# cc_gen_and_heat_pwr.net
KiCad netlist of a schematic drawn in Altium Designer
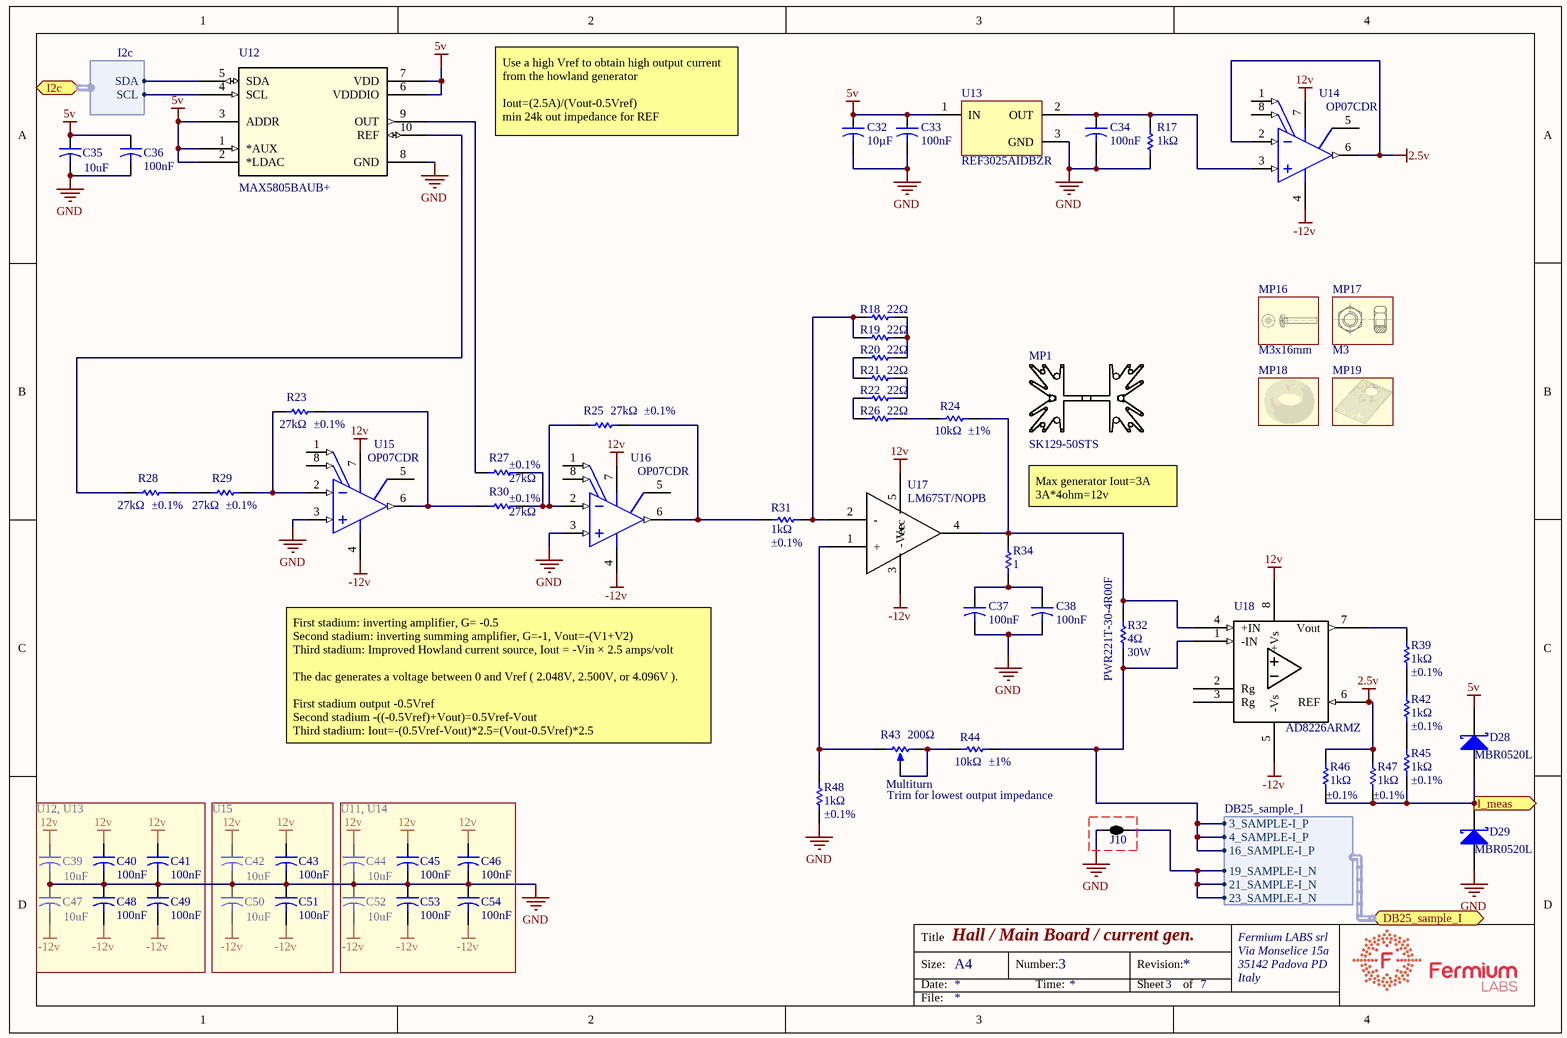
[diagram p0: cc_gen_and_heat_pwr.SchDoc]

(export (version "E")
  (design (tool "Eeschema 10.0.6"))
  (components
    (comp (ref "C32")
      (value "~")
      (footprint "Passives:CAP 1206/3216")
      (description "Capacitor")
      (fields
        (field (name "MANUFACTURER") "SAMSUNG")
        (field (name "MANUFACTURER PART NUMBER") "CL31A106KAHNNNE")
        (field (name "CAPACITANCE") "10µF")
        (field (name "PUBLISHER") "Altium Limited")
      )
      (libsource (lib "Miscellaneous Devices") (part "Cap2"))
    )
    (comp (ref "C33")
      (value "~")
      (footprint "Passives:CAP 0805/2012")
      (description "Capacitor")
      (fields
        (field (name "CAPACITANCE") "100nF")
        (field (name "MANUFACTURER") "YAGEO")
        (field (name "MANUFACTURER PART NUMBER") "CC0805JRX7R9BB104")
      )
      (libsource (lib "Miscellaneous Devices") (part "Cap2"))
    )
    (comp (ref "C34")
      (value "~")
      (footprint "Passives:CAP 0805/2012")
      (description "Capacitor")
      (fields
        (field (name "CAPACITANCE") "100nF")
        (field (name "MANUFACTURER") "YAGEO")
        (field (name "MANUFACTURER PART NUMBER") "CC0805JRX7R9BB104")
      )
      (libsource (lib "Miscellaneous Devices") (part "Cap2"))
    )
    (comp (ref "C35")
      (value "10uF")
      (footprint "Passives:CAP 1206/3216")
      (description "Capacitor")
      (fields
        (field (name "MANUFACTURER") "SAMSUNG")
        (field (name "MANUFACTURER PART NUMBER") "CL31A106KAHNNNE")
        (field (name "PUBLISHER") "Altium Limited")
      )
      (libsource (lib "Miscellaneous Devices") (part "Cap2"))
    )
    (comp (ref "C36")
      (value "~")
      (footprint "Passives:CAP 0805/2012")
      (description "Capacitor")
      (fields
        (field (name "CAPACITANCE") "100nF")
        (field (name "MANUFACTURER") "YAGEO")
        (field (name "MANUFACTURER PART NUMBER") "CC0805JRX7R9BB104")
      )
      (libsource (lib "") (part "Cap2_1"))
    )
    (comp (ref "C37")
      (value "~")
      (footprint "Passives:CAP 0805/2012")
      (description "Capacitor")
      (fields
        (field (name "CAPACITANCE") "100nF")
        (field (name "MANUFACTURER") "YAGEO")
        (field (name "MANUFACTURER PART NUMBER") "CC0805JRX7R9BB104")
      )
      (libsource (lib "Miscellaneous Devices") (part "Cap2"))
    )
    (comp (ref "C38")
      (value "~")
      (footprint "Passives:CAP 0805/2012")
      (description "Capacitor")
      (fields
        (field (name "CAPACITANCE") "100nF")
        (field (name "MANUFACTURER") "YAGEO")
        (field (name "MANUFACTURER PART NUMBER") "CC0805JRX7R9BB104")
      )
      (libsource (lib "Miscellaneous Devices") (part "Cap2"))
    )
    (comp (ref "C39")
      (value "10uF")
      (footprint "Passives:CAP 1206/3216")
      (description "Capacitor")
      (fields
        (field (name "MANUFACTURER") "SAMSUNG")
        (field (name "MANUFACTURER PART NUMBER") "CL31A106KAHNNNE")
        (field (name "PUBLISHER") "Altium Limited")
      )
      (libsource (lib "Miscellaneous Devices") (part "Cap2"))
    )
    (comp (ref "C40")
      (value "~")
      (footprint "Passives:CAP 0805/2012")
      (description "Capacitor")
      (fields
        (field (name "CAPACITANCE") "100nF")
        (field (name "MANUFACTURER") "YAGEO")
        (field (name "MANUFACTURER PART NUMBER") "CC0805JRX7R9BB104")
      )
      (libsource (lib "") (part "Cap2_1"))
    )
    (comp (ref "C41")
      (value "~")
      (footprint "Passives:CAP 0805/2012")
      (description "Capacitor")
      (fields
        (field (name "CAPACITANCE") "100nF")
        (field (name "MANUFACTURER") "YAGEO")
        (field (name "MANUFACTURER PART NUMBER") "CC0805JRX7R9BB104")
      )
      (libsource (lib "") (part "Cap2_1"))
    )
    (comp (ref "C42")
      (value "10uF")
      (footprint "Passives:CAP 1206/3216")
      (description "Capacitor")
      (fields
        (field (name "MANUFACTURER") "SAMSUNG")
        (field (name "MANUFACTURER PART NUMBER") "CL31A106KAHNNNE")
        (field (name "PUBLISHER") "Altium Limited")
      )
      (libsource (lib "Miscellaneous Devices") (part "Cap2"))
    )
    (comp (ref "C43")
      (value "~")
      (footprint "Passives:CAP 0805/2012")
      (description "Capacitor")
      (fields
        (field (name "CAPACITANCE") "100nF")
        (field (name "MANUFACTURER") "YAGEO")
        (field (name "MANUFACTURER PART NUMBER") "CC0805JRX7R9BB104")
      )
      (libsource (lib "") (part "Cap2_1"))
    )
    (comp (ref "C44")
      (value "10uF")
      (footprint "Passives:CAP 1206/3216")
      (description "Capacitor")
      (fields
        (field (name "MANUFACTURER") "SAMSUNG")
        (field (name "MANUFACTURER PART NUMBER") "CL31A106KAHNNNE")
        (field (name "PUBLISHER") "Altium Limited")
      )
      (libsource (lib "Miscellaneous Devices") (part "Cap2"))
    )
    (comp (ref "C45")
      (value "~")
      (footprint "Passives:CAP 0805/2012")
      (description "Capacitor")
      (fields
        (field (name "CAPACITANCE") "100nF")
        (field (name "MANUFACTURER") "YAGEO")
        (field (name "MANUFACTURER PART NUMBER") "CC0805JRX7R9BB104")
      )
      (libsource (lib "") (part "Cap2_1"))
    )
    (comp (ref "C46")
      (value "~")
      (footprint "Passives:CAP 0805/2012")
      (description "Capacitor")
      (fields
        (field (name "CAPACITANCE") "100nF")
        (field (name "MANUFACTURER") "YAGEO")
        (field (name "MANUFACTURER PART NUMBER") "CC0805JRX7R9BB104")
      )
      (libsource (lib "") (part "Cap2_1"))
    )
    (comp (ref "C47")
      (value "10uF")
      (footprint "Passives:CAP 1206/3216")
      (description "Capacitor")
      (fields
        (field (name "MANUFACTURER") "SAMSUNG")
        (field (name "MANUFACTURER PART NUMBER") "CL31A106KAHNNNE")
        (field (name "PUBLISHER") "Altium Limited")
      )
      (libsource (lib "Miscellaneous Devices") (part "Cap2"))
    )
    (comp (ref "C48")
      (value "~")
      (footprint "Passives:CAP 0805/2012")
      (description "Capacitor")
      (fields
        (field (name "CAPACITANCE") "100nF")
        (field (name "MANUFACTURER") "YAGEO")
        (field (name "MANUFACTURER PART NUMBER") "CC0805JRX7R9BB104")
      )
      (libsource (lib "") (part "Cap2_1"))
    )
    (comp (ref "C49")
      (value "~")
      (footprint "Passives:CAP 0805/2012")
      (description "Capacitor")
      (fields
        (field (name "CAPACITANCE") "100nF")
        (field (name "MANUFACTURER") "YAGEO")
        (field (name "MANUFACTURER PART NUMBER") "CC0805JRX7R9BB104")
      )
      (libsource (lib "") (part "Cap2_1"))
    )
    (comp (ref "C50")
      (value "10uF")
      (footprint "Passives:CAP 1206/3216")
      (description "Capacitor")
      (fields
        (field (name "MANUFACTURER") "SAMSUNG")
        (field (name "MANUFACTURER PART NUMBER") "CL31A106KAHNNNE")
        (field (name "PUBLISHER") "Altium Limited")
      )
      (libsource (lib "Miscellaneous Devices") (part "Cap2"))
    )
    (comp (ref "C51")
      (value "~")
      (footprint "Passives:CAP 0805/2012")
      (description "Capacitor")
      (fields
        (field (name "CAPACITANCE") "100nF")
        (field (name "MANUFACTURER") "YAGEO")
        (field (name "MANUFACTURER PART NUMBER") "CC0805JRX7R9BB104")
      )
      (libsource (lib "") (part "Cap2_1"))
    )
    (comp (ref "C52")
      (value "10uF")
      (footprint "Passives:CAP 1206/3216")
      (description "Capacitor")
      (fields
        (field (name "MANUFACTURER") "SAMSUNG")
        (field (name "MANUFACTURER PART NUMBER") "CL31A106KAHNNNE")
        (field (name "PUBLISHER") "Altium Limited")
      )
      (libsource (lib "Miscellaneous Devices") (part "Cap2"))
    )
    (comp (ref "C53")
      (value "~")
      (footprint "Passives:CAP 0805/2012")
      (description "Capacitor")
      (fields
        (field (name "CAPACITANCE") "100nF")
        (field (name "MANUFACTURER") "YAGEO")
        (field (name "MANUFACTURER PART NUMBER") "CC0805JRX7R9BB104")
      )
      (libsource (lib "") (part "Cap2_1"))
    )
    (comp (ref "C54")
      (value "~")
      (footprint "Passives:CAP 0805/2012")
      (description "Capacitor")
      (fields
        (field (name "CAPACITANCE") "100nF")
        (field (name "MANUFACTURER") "YAGEO")
        (field (name "MANUFACTURER PART NUMBER") "CC0805JRX7R9BB104")
      )
      (libsource (lib "") (part "Cap2_1"))
    )
    (comp (ref "D28")
      (value "~")
      (footprint "PBL - SMD Packages:SOD123")
      (description "Schottky Diode")
      (fields
        (field (name "SUPPLIER PART NUMBER 1") "MBR0520L")
        (field (name "MANUFACTURER") "FAIRCHILD SEMICONDUCTOR")
        (field (name "MANUFACTURER PART NUMBER") "MBR0520L")
        (field (name "PUBLISHER") "Altium Limited")
      )
      (libsource (lib "Miscellaneous Devices") (part "D Schottky"))
    )
    (comp (ref "D29")
      (value "~")
      (footprint "PBL - SMD Packages:SOD123")
      (description "Schottky Diode")
      (fields
        (field (name "SUPPLIER PART NUMBER 1") "MBR0520L")
        (field (name "MANUFACTURER") "FAIRCHILD SEMICONDUCTOR")
        (field (name "MANUFACTURER PART NUMBER") "MBR0520L")
        (field (name "PUBLISHER") "Altium Limited")
      )
      (libsource (lib "Miscellaneous Devices") (part "D Schottky"))
    )
    (comp (ref "J10")
      (value "2 way net tie junction")
      (footprint "2way_LP")
      (libsource (lib "NetTieLib") (part "2way"))
    )
    (comp (ref "MP1")
      (value "~")
      (footprint "SK129-50STS")
      (fields (field (name "MANUFACTURER PART NUMBER") "SK129-50STS"))
      (libsource (lib "custom_components") (part "SK129-63STS"))
    )
    (comp (ref "MP16")
      (value "screw-M3x25mm")
      (fields
        (field (name "MANUFACTURER PART NUMBER") "M3X16/D7985")
        (field (name "MANUFACTURER") "KRAFTBERG")
        (field (name "SIZE") "M3x16mm")
      )
      (libsource (lib "custom_components") (part "screw-M3x25mm"))
    )
    (comp (ref "MP17")
      (value "nut-M3")
      (fields
        (field (name "MANUFACTURER PART NUMBER") "1874659")
        (field (name "MANUFACTURER") "BOSSARD")
        (field (name "SIZE") "M3")
      )
      (libsource (lib "custom_components") (part "nut-M3"))
    )
    (comp (ref "MP18")
      (value "isolator-TO220")
      (fields
        (field (name "MANUFACTURER PART NUMBER") "NIPPEL-TO220/1")
        (field (name "MANUFACTURER") "NINIGI")
      )
      (libsource (lib "custom_components") (part "isolator-TO220"))
    )
    (comp (ref "MP19")
      (value "thermpad-TO220")
      (fields
        (field (name "MANUFACTURER PART NUMBER") "GS 220 4")
        (field (name "MANUFACTURER") "FISCHER ELEKTRONIK")
      )
      (libsource (lib "custom_components") (part "thermpad-TO220"))
    )
    (comp (ref "R17")
      (value "~")
      (footprint "Passives:RES 0805/2012")
      (description "Resistor")
      (fields
        (field (name "MANUFACTURER") "VIKING")
        (field (name "MANUFACTURER PART NUMBER") "AR05BTCW1001")
        (field (name "RESISTANCE") "1kΩ")
        (field (name "PUBLISHER") "Altium Limited")
      )
      (libsource (lib "Miscellaneous Devices") (part "Res1"))
    )
    (comp (ref "R18")
      (value "~")
      (footprint "Passives:RES 0805/2012")
      (description "Resistor")
      (fields
        (field (name "RESISTANCE") "22Ω")
        (field (name "MANUFACTURER") "ROYAL OHM")
        (field (name "MANUFACTURER PART NUMBER") "0805S8F220JT5E")
      )
      (libsource (lib "Miscellaneous Devices") (part "Res1"))
    )
    (comp (ref "R19")
      (value "~")
      (footprint "Passives:RES 0805/2012")
      (description "Resistor")
      (fields
        (field (name "RESISTANCE") "22Ω")
        (field (name "MANUFACTURER") "ROYAL OHM")
        (field (name "MANUFACTURER PART NUMBER") "0805S8F220JT5E")
      )
      (libsource (lib "Miscellaneous Devices") (part "Res1"))
    )
    (comp (ref "R20")
      (value "~")
      (footprint "Passives:RES 0805/2012")
      (description "Resistor")
      (fields
        (field (name "RESISTANCE") "22Ω")
        (field (name "MANUFACTURER") "ROYAL OHM")
        (field (name "MANUFACTURER PART NUMBER") "0805S8F220JT5E")
      )
      (libsource (lib "Miscellaneous Devices") (part "Res1"))
    )
    (comp (ref "R21")
      (value "~")
      (footprint "Passives:RES 0805/2012")
      (description "Resistor")
      (fields
        (field (name "RESISTANCE") "22Ω")
        (field (name "MANUFACTURER") "ROYAL OHM")
        (field (name "MANUFACTURER PART NUMBER") "0805S8F220JT5E")
      )
      (libsource (lib "Miscellaneous Devices") (part "Res1"))
    )
    (comp (ref "R22")
      (value "~")
      (footprint "Passives:RES 0805/2012")
      (description "Resistor")
      (fields
        (field (name "RESISTANCE") "22Ω")
        (field (name "MANUFACTURER") "ROYAL OHM")
        (field (name "MANUFACTURER PART NUMBER") "0805S8F220JT5E")
      )
      (libsource (lib "Miscellaneous Devices") (part "Res1"))
    )
    (comp (ref "R23")
      (value "~")
      (footprint "Passives:RES 0805/2012")
      (description "Resistor")
      (fields
        (field (name "MANUFACTURER") "VIKING")
        (field (name "MANUFACTURER PART NUMBER") "AR05BTCW2702")
        (field (name "RESISTANCE") "27kΩ")
        (field (name "TOLERANCE") "±0.1%")
      )
      (libsource (lib "Miscellaneous Devices") (part "Res1"))
    )
    (comp (ref "R24")
      (value "~")
      (footprint "Passives:RES 0805/2012")
      (description "Resistor")
      (fields
        (field (name "MANUFACTURER") "ROYAL OHM")
        (field (name "MANUFACTURER PART NUMBER") "0805S8F1002T5E")
        (field (name "RESISTANCE") "10kΩ")
        (field (name "TOLERANCE") "±1%")
      )
      (libsource (lib "Miscellaneous Devices") (part "Res1"))
    )
    (comp (ref "R25")
      (value "~")
      (footprint "Passives:RES 0805/2012")
      (description "Resistor")
      (fields
        (field (name "MANUFACTURER") "VIKING")
        (field (name "MANUFACTURER PART NUMBER") "AR05BTCW2702")
        (field (name "RESISTANCE") "27kΩ")
        (field (name "TOLERANCE") "±0.1%")
      )
      (libsource (lib "Miscellaneous Devices") (part "Res1"))
    )
    (comp (ref "R26")
      (value "~")
      (footprint "Passives:RES 0805/2012")
      (description "Resistor")
      (fields
        (field (name "RESISTANCE") "22Ω")
        (field (name "MANUFACTURER") "ROYAL OHM")
        (field (name "MANUFACTURER PART NUMBER") "0805S8F220JT5E")
      )
      (libsource (lib "Miscellaneous Devices") (part "Res1"))
    )
    (comp (ref "R27")
      (value "~")
      (footprint "Passives:RES 0805/2012")
      (description "Resistor")
      (fields
        (field (name "MANUFACTURER") "VIKING")
        (field (name "MANUFACTURER PART NUMBER") "AR05BTCW2702")
        (field (name "RESISTANCE") "27kΩ")
        (field (name "TOLERANCE") "±0.1%")
      )
      (libsource (lib "Miscellaneous Devices") (part "Res1"))
    )
    (comp (ref "R28")
      (value "~")
      (footprint "Passives:RES 0805/2012")
      (description "Resistor")
      (fields
        (field (name "MANUFACTURER") "VIKING")
        (field (name "MANUFACTURER PART NUMBER") "AR05BTCW2702")
        (field (name "RESISTANCE") "27kΩ")
        (field (name "TOLERANCE") "±0.1%")
      )
      (libsource (lib "Miscellaneous Devices") (part "Res1"))
    )
    (comp (ref "R29")
      (value "~")
      (footprint "Passives:RES 0805/2012")
      (description "Resistor")
      (fields
        (field (name "MANUFACTURER") "VIKING")
        (field (name "MANUFACTURER PART NUMBER") "AR05BTCW2702")
        (field (name "RESISTANCE") "27kΩ")
        (field (name "TOLERANCE") "±0.1%")
      )
      (libsource (lib "Miscellaneous Devices") (part "Res1"))
    )
    (comp (ref "R30")
      (value "~")
      (footprint "Passives:RES 0805/2012")
      (description "Resistor")
      (fields
        (field (name "MANUFACTURER") "VIKING")
        (field (name "MANUFACTURER PART NUMBER") "AR05BTCW2702")
        (field (name "RESISTANCE") "27kΩ")
        (field (name "TOLERANCE") "±0.1%")
      )
      (libsource (lib "Miscellaneous Devices") (part "Res1"))
    )
    (comp (ref "R31")
      (value "~")
      (footprint "Passives:RES 0805/2012")
      (description "Resistor")
      (fields
        (field (name "MANUFACTURER") "VIKING")
        (field (name "MANUFACTURER PART NUMBER") "AR05BTCW1001")
        (field (name "RESISTANCE") "1kΩ")
        (field (name "TOLERANCE") "±0.1%")
        (field (name "PUBLISHER") "Altium Limited")
      )
      (libsource (lib "Miscellaneous Devices") (part "Res1"))
    )
    (comp (ref "R32")
      (value "~")
      (footprint "to220-2pin")
      (description "Resistor")
      (fields
        (field (name "RESISTANCE") "4Ω")
        (field (name "POWER") "30W")
        (field (name "MANUFACTURER PART NUMBER") "PWR221T-30-4R00F")
      )
      (libsource (lib "Miscellaneous Devices") (part "Res1"))
    )
    (comp (ref "R34")
      (value "~")
      (footprint "Passives:STACKPOLE CSRN2512")
      (description "Resistor")
      (fields (field (name "RESISTANCE") "1") (field (name "MANUFACTURER") "ROYAL OHM"))
      (libsource (lib "Miscellaneous Devices") (part "Res1"))
    )
    (comp (ref "R39")
      (value "~")
      (footprint "Passives:RES 0805/2012")
      (description "Resistor")
      (fields
        (field (name "MANUFACTURER") "VIKING")
        (field (name "MANUFACTURER PART NUMBER") "AR05BTCW1001")
        (field (name "RESISTANCE") "1kΩ")
        (field (name "TOLERANCE") "±0.1%")
        (field (name "PUBLISHER") "Altium Limited")
      )
      (libsource (lib "Miscellaneous Devices") (part "Res1"))
    )
    (comp (ref "R42")
      (value "~")
      (footprint "Passives:RES 0805/2012")
      (description "Resistor")
      (fields
        (field (name "MANUFACTURER") "VIKING")
        (field (name "MANUFACTURER PART NUMBER") "AR05BTCW1001")
        (field (name "RESISTANCE") "1kΩ")
        (field (name "TOLERANCE") "±0.1%")
        (field (name "PUBLISHER") "Altium Limited")
      )
      (libsource (lib "Miscellaneous Devices") (part "Res1"))
    )
    (comp (ref "R43")
      (value "Multiturn")
      (footprint "trimmer-multiturn")
      (description "Potentiometer")
      (fields
        (field (name "MANUFACTURER") "SR PASSIVES")
        (field (name "MANUFACTURER PART NUMBER") "T910W-200R")
        (field (name "RESISTANCE") "200Ω")
      )
      (libsource (lib "Miscellaneous Devices") (part "RPot"))
    )
    (comp (ref "R44")
      (value "~")
      (footprint "Passives:RES 0805/2012")
      (description "Resistor")
      (fields
        (field (name "MANUFACTURER") "ROYAL OHM")
        (field (name "MANUFACTURER PART NUMBER") "0805S8F1002T5E")
        (field (name "RESISTANCE") "10kΩ")
        (field (name "TOLERANCE") "±1%")
      )
      (libsource (lib "Miscellaneous Devices") (part "Res1"))
    )
    (comp (ref "R45")
      (value "~")
      (footprint "Passives:RES 0805/2012")
      (description "Resistor")
      (fields
        (field (name "MANUFACTURER") "VIKING")
        (field (name "MANUFACTURER PART NUMBER") "AR05BTCW1001")
        (field (name "RESISTANCE") "1kΩ")
        (field (name "TOLERANCE") "±0.1%")
        (field (name "PUBLISHER") "Altium Limited")
      )
      (libsource (lib "Miscellaneous Devices") (part "Res1"))
    )
    (comp (ref "R46")
      (value "~")
      (footprint "Passives:RES 0805/2012")
      (description "Resistor")
      (fields
        (field (name "MANUFACTURER") "VIKING")
        (field (name "MANUFACTURER PART NUMBER") "AR05BTCW1001")
        (field (name "RESISTANCE") "1kΩ")
        (field (name "TOLERANCE") "±0.1%")
        (field (name "PUBLISHER") "Altium Limited")
      )
      (libsource (lib "Miscellaneous Devices") (part "Res1"))
    )
    (comp (ref "R47")
      (value "~")
      (footprint "Passives:RES 0805/2012")
      (description "Resistor")
      (fields
        (field (name "MANUFACTURER") "VIKING")
        (field (name "MANUFACTURER PART NUMBER") "AR05BTCW1001")
        (field (name "RESISTANCE") "1kΩ")
        (field (name "TOLERANCE") "±0.1%")
        (field (name "PUBLISHER") "Altium Limited")
      )
      (libsource (lib "Miscellaneous Devices") (part "Res1"))
    )
    (comp (ref "R48")
      (value "~")
      (footprint "Passives:RES 0805/2012")
      (description "Resistor")
      (fields
        (field (name "MANUFACTURER") "VIKING")
        (field (name "MANUFACTURER PART NUMBER") "AR05BTCW1001")
        (field (name "RESISTANCE") "1kΩ")
        (field (name "TOLERANCE") "±0.1%")
        (field (name "PUBLISHER") "Altium Limited")
      )
      (libsource (lib "Miscellaneous Devices") (part "Res1"))
    )
    (comp (ref "U12")
      (value "~")
      (footprint "21-0061L")
      (description "Imported")
      (fields
        (field (name "MANUFACTURER") "Maxim Integrated")
        (field (name "MANUFACTURER PART NUMBER") "MAX5805BAUB+")
        (field (name "COPYRIGHT") "Copyright (C) 2015 Accelerated Designs. All rights reserved")
      )
      (libsource (lib "MAX5805") (part "MAX5805AAUB+"))
    )
    (comp (ref "U13")
      (value "~")
      (footprint "TI-DBZ3_N")
      (description "Voltage reference, 2.5V")
      (fields
        (field (name "MANUFACTURER") "Texas Instruments")
        (field (name "MANUFACTURER PART NUMBER") "REF3025AIDBZR")
      )
      (libsource (lib "TI Power Management Series Voltage Reference") (part "REF3025AIDBZR"))
    )
    (comp (ref "U14")
      (value "~")
      (footprint "TI-D8_N")
      (fields
        (field (name "SUPPLIER PART NUMBER 1") "OP07CDR")
        (field (name "MANUFACTURER") "TEXAS INSTRUMENTS")
        (field (name "MANUFACTURER PART NUMBER") "OP07CDR")
      )
      (libsource (lib "TI Amplifiers and Linear Operational Amplifier General Purpose") (part "OP07CDR"))
    )
    (comp (ref "U15")
      (value "~")
      (footprint "TI-D8_N")
      (fields
        (field (name "SUPPLIER PART NUMBER 1") "OP07CDR")
        (field (name "MANUFACTURER") "TEXAS INSTRUMENTS")
        (field (name "MANUFACTURER PART NUMBER") "OP07CDR")
      )
      (libsource (lib "TI Amplifiers and Linear Operational Amplifier General Purpose") (part "OP07CDR"))
    )
    (comp (ref "U16")
      (value "~")
      (footprint "TI-D8_N")
      (fields
        (field (name "SUPPLIER PART NUMBER 1") "OP07CDR")
        (field (name "MANUFACTURER") "TEXAS INSTRUMENTS")
        (field (name "MANUFACTURER PART NUMBER") "OP07CDR")
      )
      (libsource (lib "TI Amplifiers and Linear Operational Amplifier General Purpose") (part "OP07CDR"))
    )
    (comp (ref "U17")
      (value "~")
      (footprint "PBL - THD Packages:TO-220-5")
      (fields
        (field (name "SUPPLIER PART NUMBER 1") "LM675T/NOPB")
        (field (name "MANUFACTURER") "TEXAS INSTRUMENTS")
        (field (name "MANUFACTURER PART NUMBER") "LM675T/NOPB")
      )
      (libsource (lib "custom_components") (part "lm675"))
    )
    (comp (ref "U18")
      (value "~")
      (footprint "MSOP_MO-187-AA AD8220")
      (description "Instrumentation amplifier")
      (fields
        (field (name "MANUFACTURER") "Analog Devices")
        (field (name "MANUFACTURER PART NUMBER") "AD8226ARMZ")
      )
      (libsource (lib "custom_components") (part "AD8226"))
    )
  )
  (nets
    (net (code "3") (name "-12v") (class "Default")
      (node (ref "C47") (pin "2") (pinfunction "2_2") (pintype "passive"))
      (node (ref "C48") (pin "2") (pinfunction "2_2") (pintype "passive"))
      (node (ref "C49") (pin "2") (pinfunction "2_2") (pintype "passive"))
      (node (ref "C50") (pin "2") (pinfunction "2_2") (pintype "passive"))
      (node (ref "C51") (pin "2") (pinfunction "2_2") (pintype "passive"))
      (node (ref "C52") (pin "2") (pinfunction "2_2") (pintype "passive"))
      (node (ref "C53") (pin "2") (pinfunction "2_2") (pintype "passive"))
      (node (ref "C54") (pin "2") (pinfunction "2_2") (pintype "passive"))
      (node (ref "U14") (pin "4") (pinfunction "VCC-_4") (pintype "power_in"))
      (node (ref "U15") (pin "4") (pinfunction "VCC-_4") (pintype "power_in"))
      (node (ref "U16") (pin "4") (pinfunction "VCC-_4") (pintype "power_in"))
      (node (ref "U17") (pin "3") (pinfunction "-Vee_3") (pintype "passive"))
      (node (ref "U18") (pin "5") (pinfunction "-Vs_5") (pintype "power_in"))
    )
    (net (code "4") (name "/16_SAMPLE-I_P") (class "Default")
      (node (ref "R32") (pin "2") (pinfunction "2_2") (pintype "passive"))
      (node (ref "R44") (pin "1") (pinfunction "1_1") (pintype "passive"))
      (node (ref "U18") (pin "1") (pinfunction "-IN_1") (pintype "input"))
    )
    (net (code "5") (name "/19_SAMPLE-I_N") (class "Default")
      (node (ref "J10") (pin "2") (pinfunction "2_2") (pintype "passive"))
    )
    (net (code "6") (name "/I_meas") (class "Default")
      (node (ref "D28") (pin "A") (pinfunction "A_A") (pintype "passive"))
      (node (ref "D29") (pin "K") (pinfunction "K_K") (pintype "passive"))
      (node (ref "R45") (pin "1") (pinfunction "1_1") (pintype "passive"))
      (node (ref "R46") (pin "1") (pinfunction "1_1") (pintype "passive"))
      (node (ref "R47") (pin "1") (pinfunction "1_1") (pintype "passive"))
    )
    (net (code "7") (name "/SCL") (class "Default")
      (node (ref "U12") (pin "4") (pinfunction "SCL_4") (pintype "input"))
    )
    (net (code "8") (name "/SDA") (class "Default")
      (node (ref "U12") (pin "5") (pinfunction "SDA_5") (pintype "bidirectional"))
    )
    (net (code "11") (name "2.5v") (class "Default")
      (node (ref "R46") (pin "2") (pinfunction "2_2") (pintype "passive"))
      (node (ref "R47") (pin "2") (pinfunction "2_2") (pintype "passive"))
      (node (ref "U14") (pin "2") (pinfunction "IN-_2") (pintype "input"))
      (node (ref "U14") (pin "6") (pinfunction "OUT_6") (pintype "output"))
      (node (ref "U18") (pin "6") (pinfunction "REF_6") (pintype "input"))
    )
    (net (code "12") (name "5v") (class "Default")
      (node (ref "C32") (pin "1") (pinfunction "1_1") (pintype "passive"))
      (node (ref "C33") (pin "1") (pinfunction "1_1") (pintype "passive"))
      (node (ref "C35") (pin "1") (pinfunction "1_1") (pintype "passive"))
      (node (ref "C36") (pin "1") (pinfunction "1_1") (pintype "passive"))
      (node (ref "D28") (pin "K") (pinfunction "K_K") (pintype "passive"))
      (node (ref "U12") (pin "1") (pinfunction "*AUX_1") (pintype "input"))
      (node (ref "U12") (pin "2") (pinfunction "*LDAC_2") (pintype "passive"))
      (node (ref "U12") (pin "3") (pinfunction "ADDR_3") (pintype "passive"))
      (node (ref "U12") (pin "6") (pinfunction "VDDDIO_6") (pintype "power_in"))
      (node (ref "U12") (pin "7") (pinfunction "VDD_7") (pintype "power_in"))
      (node (ref "U13") (pin "1") (pinfunction "IN_1") (pintype "power_in"))
    )
    (net (code "13") (name "12v") (class "Default")
      (node (ref "C39") (pin "1") (pinfunction "1_1") (pintype "passive"))
      (node (ref "C40") (pin "1") (pinfunction "1_1") (pintype "passive"))
      (node (ref "C41") (pin "1") (pinfunction "1_1") (pintype "passive"))
      (node (ref "C42") (pin "1") (pinfunction "1_1") (pintype "passive"))
      (node (ref "C43") (pin "1") (pinfunction "1_1") (pintype "passive"))
      (node (ref "C44") (pin "1") (pinfunction "1_1") (pintype "passive"))
      (node (ref "C45") (pin "1") (pinfunction "1_1") (pintype "passive"))
      (node (ref "C46") (pin "1") (pinfunction "1_1") (pintype "passive"))
      (node (ref "U14") (pin "7") (pinfunction "VCC+_7") (pintype "power_in"))
      (node (ref "U15") (pin "7") (pinfunction "VCC+_7") (pintype "power_in"))
      (node (ref "U16") (pin "7") (pinfunction "VCC+_7") (pintype "power_in"))
      (node (ref "U17") (pin "5") (pinfunction "Vcc_5") (pintype "passive"))
      (node (ref "U18") (pin "8") (pinfunction "+Vs_8") (pintype "power_in"))
    )
    (net (code "14") (name "GND") (class "Default")
      (node (ref "C32") (pin "2") (pinfunction "2_2") (pintype "passive"))
      (node (ref "C33") (pin "2") (pinfunction "2_2") (pintype "passive"))
      (node (ref "C34") (pin "2") (pinfunction "2_2") (pintype "passive"))
      (node (ref "C35") (pin "2") (pinfunction "2_2") (pintype "passive"))
      (node (ref "C36") (pin "2") (pinfunction "2_2") (pintype "passive"))
      (node (ref "C37") (pin "2") (pinfunction "2_2") (pintype "passive"))
      (node (ref "C38") (pin "2") (pinfunction "2_2") (pintype "passive"))
      (node (ref "C39") (pin "2") (pinfunction "2_2") (pintype "passive"))
      (node (ref "C40") (pin "2") (pinfunction "2_2") (pintype "passive"))
      (node (ref "C41") (pin "2") (pinfunction "2_2") (pintype "passive"))
      (node (ref "C42") (pin "2") (pinfunction "2_2") (pintype "passive"))
      (node (ref "C43") (pin "2") (pinfunction "2_2") (pintype "passive"))
      (node (ref "C44") (pin "2") (pinfunction "2_2") (pintype "passive"))
      (node (ref "C45") (pin "2") (pinfunction "2_2") (pintype "passive"))
      (node (ref "C46") (pin "2") (pinfunction "2_2") (pintype "passive"))
      (node (ref "C47") (pin "1") (pinfunction "1_1") (pintype "passive"))
      (node (ref "C48") (pin "1") (pinfunction "1_1") (pintype "passive"))
      (node (ref "C49") (pin "1") (pinfunction "1_1") (pintype "passive"))
      (node (ref "C50") (pin "1") (pinfunction "1_1") (pintype "passive"))
      (node (ref "C51") (pin "1") (pinfunction "1_1") (pintype "passive"))
      (node (ref "C52") (pin "1") (pinfunction "1_1") (pintype "passive"))
      (node (ref "C53") (pin "1") (pinfunction "1_1") (pintype "passive"))
      (node (ref "C54") (pin "1") (pinfunction "1_1") (pintype "passive"))
      (node (ref "D29") (pin "A") (pinfunction "A_A") (pintype "passive"))
      (node (ref "J10") (pin "1") (pinfunction "1_1") (pintype "passive"))
      (node (ref "R17") (pin "2") (pinfunction "2_2") (pintype "passive"))
      (node (ref "R48") (pin "2") (pinfunction "2_2") (pintype "passive"))
      (node (ref "U12") (pin "8") (pinfunction "GND_8") (pintype "power_in"))
      (node (ref "U13") (pin "3") (pinfunction "GND_3") (pintype "power_in"))
      (node (ref "U15") (pin "3") (pinfunction "IN+_3") (pintype "input"))
      (node (ref "U16") (pin "3") (pinfunction "IN+_3") (pintype "input"))
    )
    (net (code "15") (name "Net-(C37-Pad1)") (class "Default")
      (node (ref "C37") (pin "1") (pinfunction "1_1") (pintype "passive"))
      (node (ref "C38") (pin "1") (pinfunction "1_1") (pintype "passive"))
      (node (ref "R34") (pin "1") (pinfunction "1_1") (pintype "passive"))
    )
    (net (code "16") (name "Net-(R18-Pad1)") (class "Default")
      (node (ref "R18") (pin "1") (pinfunction "1_1") (pintype "passive"))
      (node (ref "R19") (pin "1") (pinfunction "1_1") (pintype "passive"))
      (node (ref "R20") (pin "1") (pinfunction "1_1") (pintype "passive"))
    )
    (net (code "17") (name "Net-(R20-Pad2)") (class "Default")
      (node (ref "R20") (pin "2") (pinfunction "2_2") (pintype "passive"))
      (node (ref "R21") (pin "2") (pinfunction "2_2") (pintype "passive"))
    )
    (net (code "18") (name "Net-(R21-Pad1)") (class "Default")
      (node (ref "R21") (pin "1") (pinfunction "1_1") (pintype "passive"))
      (node (ref "R22") (pin "1") (pinfunction "1_1") (pintype "passive"))
    )
    (net (code "19") (name "Net-(R22-Pad2)") (class "Default")
      (node (ref "R22") (pin "2") (pinfunction "2_2") (pintype "passive"))
      (node (ref "R26") (pin "2") (pinfunction "2_2") (pintype "passive"))
    )
    (net (code "20") (name "Net-(R24-Pad2)") (class "Default")
      (node (ref "R24") (pin "2") (pinfunction "2_2") (pintype "passive"))
      (node (ref "R26") (pin "1") (pinfunction "1_1") (pintype "passive"))
    )
    (net (code "21") (name "Net-(R28-Pad1)") (class "Default")
      (node (ref "R28") (pin "1") (pinfunction "1_1") (pintype "passive"))
      (node (ref "R29") (pin "2") (pinfunction "2_2") (pintype "passive"))
    )
    (net (code "22") (name "Net-(R39-Pad1)") (class "Default")
      (node (ref "R39") (pin "1") (pinfunction "1_1") (pintype "passive"))
      (node (ref "R42") (pin "2") (pinfunction "2_2") (pintype "passive"))
    )
    (net (code "23") (name "Net-(R42-Pad1)") (class "Default")
      (node (ref "R42") (pin "1") (pinfunction "1_1") (pintype "passive"))
      (node (ref "R45") (pin "2") (pinfunction "2_2") (pintype "passive"))
    )
    (net (code "24") (name "Net-(R43-Pad2)") (class "Default")
      (node (ref "R43") (pin "2") (pinfunction "2_2") (pintype "passive"))
      (node (ref "R43") (pin "3") (pinfunction "3_3") (pintype "passive"))
      (node (ref "R44") (pin "2") (pinfunction "2_2") (pintype "passive"))
    )
    (net (code "25") (name "Net-(U12-OUT)") (class "Default")
      (node (ref "R27") (pin "2") (pinfunction "2_2") (pintype "passive"))
      (node (ref "U12") (pin "9") (pinfunction "OUT_9") (pintype "output"))
    )
    (net (code "26") (name "Net-(U12-REF)") (class "Default")
      (node (ref "R28") (pin "2") (pinfunction "2_2") (pintype "passive"))
      (node (ref "U12") (pin "10") (pinfunction "REF_10") (pintype "bidirectional"))
    )
    (net (code "27") (name "Net-(U13-OUT)") (class "Default")
      (node (ref "C34") (pin "1") (pinfunction "1_1") (pintype "passive"))
      (node (ref "R17") (pin "1") (pinfunction "1_1") (pintype "passive"))
      (node (ref "U13") (pin "2") (pinfunction "OUT_2") (pintype "power_in"))
      (node (ref "U14") (pin "3") (pinfunction "IN+_3") (pintype "input"))
    )
    (net (code "28") (name "Net-(U15-IN-)") (class "Default")
      (node (ref "R23") (pin "2") (pinfunction "2_2") (pintype "passive"))
      (node (ref "R29") (pin "1") (pinfunction "1_1") (pintype "passive"))
      (node (ref "U15") (pin "2") (pinfunction "IN-_2") (pintype "input"))
    )
    (net (code "29") (name "Net-(U15-OUT)") (class "Default")
      (node (ref "R23") (pin "1") (pinfunction "1_1") (pintype "passive"))
      (node (ref "R30") (pin "2") (pinfunction "2_2") (pintype "passive"))
      (node (ref "U15") (pin "6") (pinfunction "OUT_6") (pintype "output"))
    )
    (net (code "30") (name "Net-(U16-IN-)") (class "Default")
      (node (ref "R25") (pin "2") (pinfunction "2_2") (pintype "passive"))
      (node (ref "R27") (pin "1") (pinfunction "1_1") (pintype "passive"))
      (node (ref "R30") (pin "1") (pinfunction "1_1") (pintype "passive"))
      (node (ref "U16") (pin "2") (pinfunction "IN-_2") (pintype "input"))
    )
    (net (code "31") (name "Net-(U16-OUT)") (class "Default")
      (node (ref "R25") (pin "1") (pinfunction "1_1") (pintype "passive"))
      (node (ref "R31") (pin "1") (pinfunction "1_1") (pintype "passive"))
      (node (ref "U16") (pin "6") (pinfunction "OUT_6") (pintype "output"))
    )
    (net (code "32") (name "Net-(U17-+)") (class "Default")
      (node (ref "R43") (pin "1") (pinfunction "1_1") (pintype "passive"))
      (node (ref "R48") (pin "1") (pinfunction "1_1") (pintype "passive"))
      (node (ref "U17") (pin "1") (pinfunction "+_1") (pintype "passive"))
    )
    (net (code "33") (name "Net-(U17--)") (class "Default")
      (node (ref "R18") (pin "2") (pinfunction "2_2") (pintype "passive"))
      (node (ref "R19") (pin "2") (pinfunction "2_2") (pintype "passive"))
      (node (ref "R31") (pin "2") (pinfunction "2_2") (pintype "passive"))
      (node (ref "U17") (pin "2") (pinfunction "-_2") (pintype "passive"))
    )
    (net (code "34") (name "Net-(U17-OUT)") (class "Default")
      (node (ref "R24") (pin "1") (pinfunction "1_1") (pintype "passive"))
      (node (ref "R32") (pin "1") (pinfunction "1_1") (pintype "passive"))
      (node (ref "R34") (pin "2") (pinfunction "2_2") (pintype "passive"))
      (node (ref "U17") (pin "4") (pinfunction "OUT_4") (pintype "passive"))
      (node (ref "U18") (pin "4") (pinfunction "+IN_4") (pintype "input"))
    )
    (net (code "35") (name "Net-(U18-Vout)") (class "Default")
      (node (ref "R39") (pin "2") (pinfunction "2_2") (pintype "passive"))
      (node (ref "U18") (pin "7") (pinfunction "Vout_7") (pintype "output"))
    )
    (net (code "36") (name "unconnected-(U14-NC-Pad5)") (class "Default")
      (node (ref "U14") (pin "5") (pinfunction "NC_5") (pintype "passive"))
    )
    (net (code "37") (name "unconnected-(U14-OFFSET_N1-Pad1)") (class "Default")
      (node (ref "U14") (pin "1") (pinfunction "OFFSET_N1_1") (pintype "input"))
    )
    (net (code "38") (name "unconnected-(U14-OFFSET_N2-Pad8)") (class "Default")
      (node (ref "U14") (pin "8") (pinfunction "OFFSET_N2_8") (pintype "input"))
    )
    (net (code "39") (name "unconnected-(U15-NC-Pad5)") (class "Default")
      (node (ref "U15") (pin "5") (pinfunction "NC_5") (pintype "passive"))
    )
    (net (code "40") (name "unconnected-(U15-OFFSET_N1-Pad1)") (class "Default")
      (node (ref "U15") (pin "1") (pinfunction "OFFSET_N1_1") (pintype "input"))
    )
    (net (code "41") (name "unconnected-(U15-OFFSET_N2-Pad8)") (class "Default")
      (node (ref "U15") (pin "8") (pinfunction "OFFSET_N2_8") (pintype "input"))
    )
    (net (code "42") (name "unconnected-(U16-NC-Pad5)") (class "Default")
      (node (ref "U16") (pin "5") (pinfunction "NC_5") (pintype "passive"))
    )
    (net (code "43") (name "unconnected-(U16-OFFSET_N1-Pad1)") (class "Default")
      (node (ref "U16") (pin "1") (pinfunction "OFFSET_N1_1") (pintype "input"))
    )
    (net (code "44") (name "unconnected-(U16-OFFSET_N2-Pad8)") (class "Default")
      (node (ref "U16") (pin "8") (pinfunction "OFFSET_N2_8") (pintype "input"))
    )
    (net (code "45") (name "unconnected-(U18-Rg-Pad2)") (class "Default")
      (node (ref "U18") (pin "2") (pinfunction "Rg_2") (pintype "passive"))
    )
    (net (code "46") (name "unconnected-(U18-Rg-Pad3)") (class "Default")
      (node (ref "U18") (pin "3") (pinfunction "Rg_3") (pintype "passive"))
    )
  )
)
